# T35_3_POWERSUPPLY.net
KiCad netlist of a schematic drawn in Altium Designer
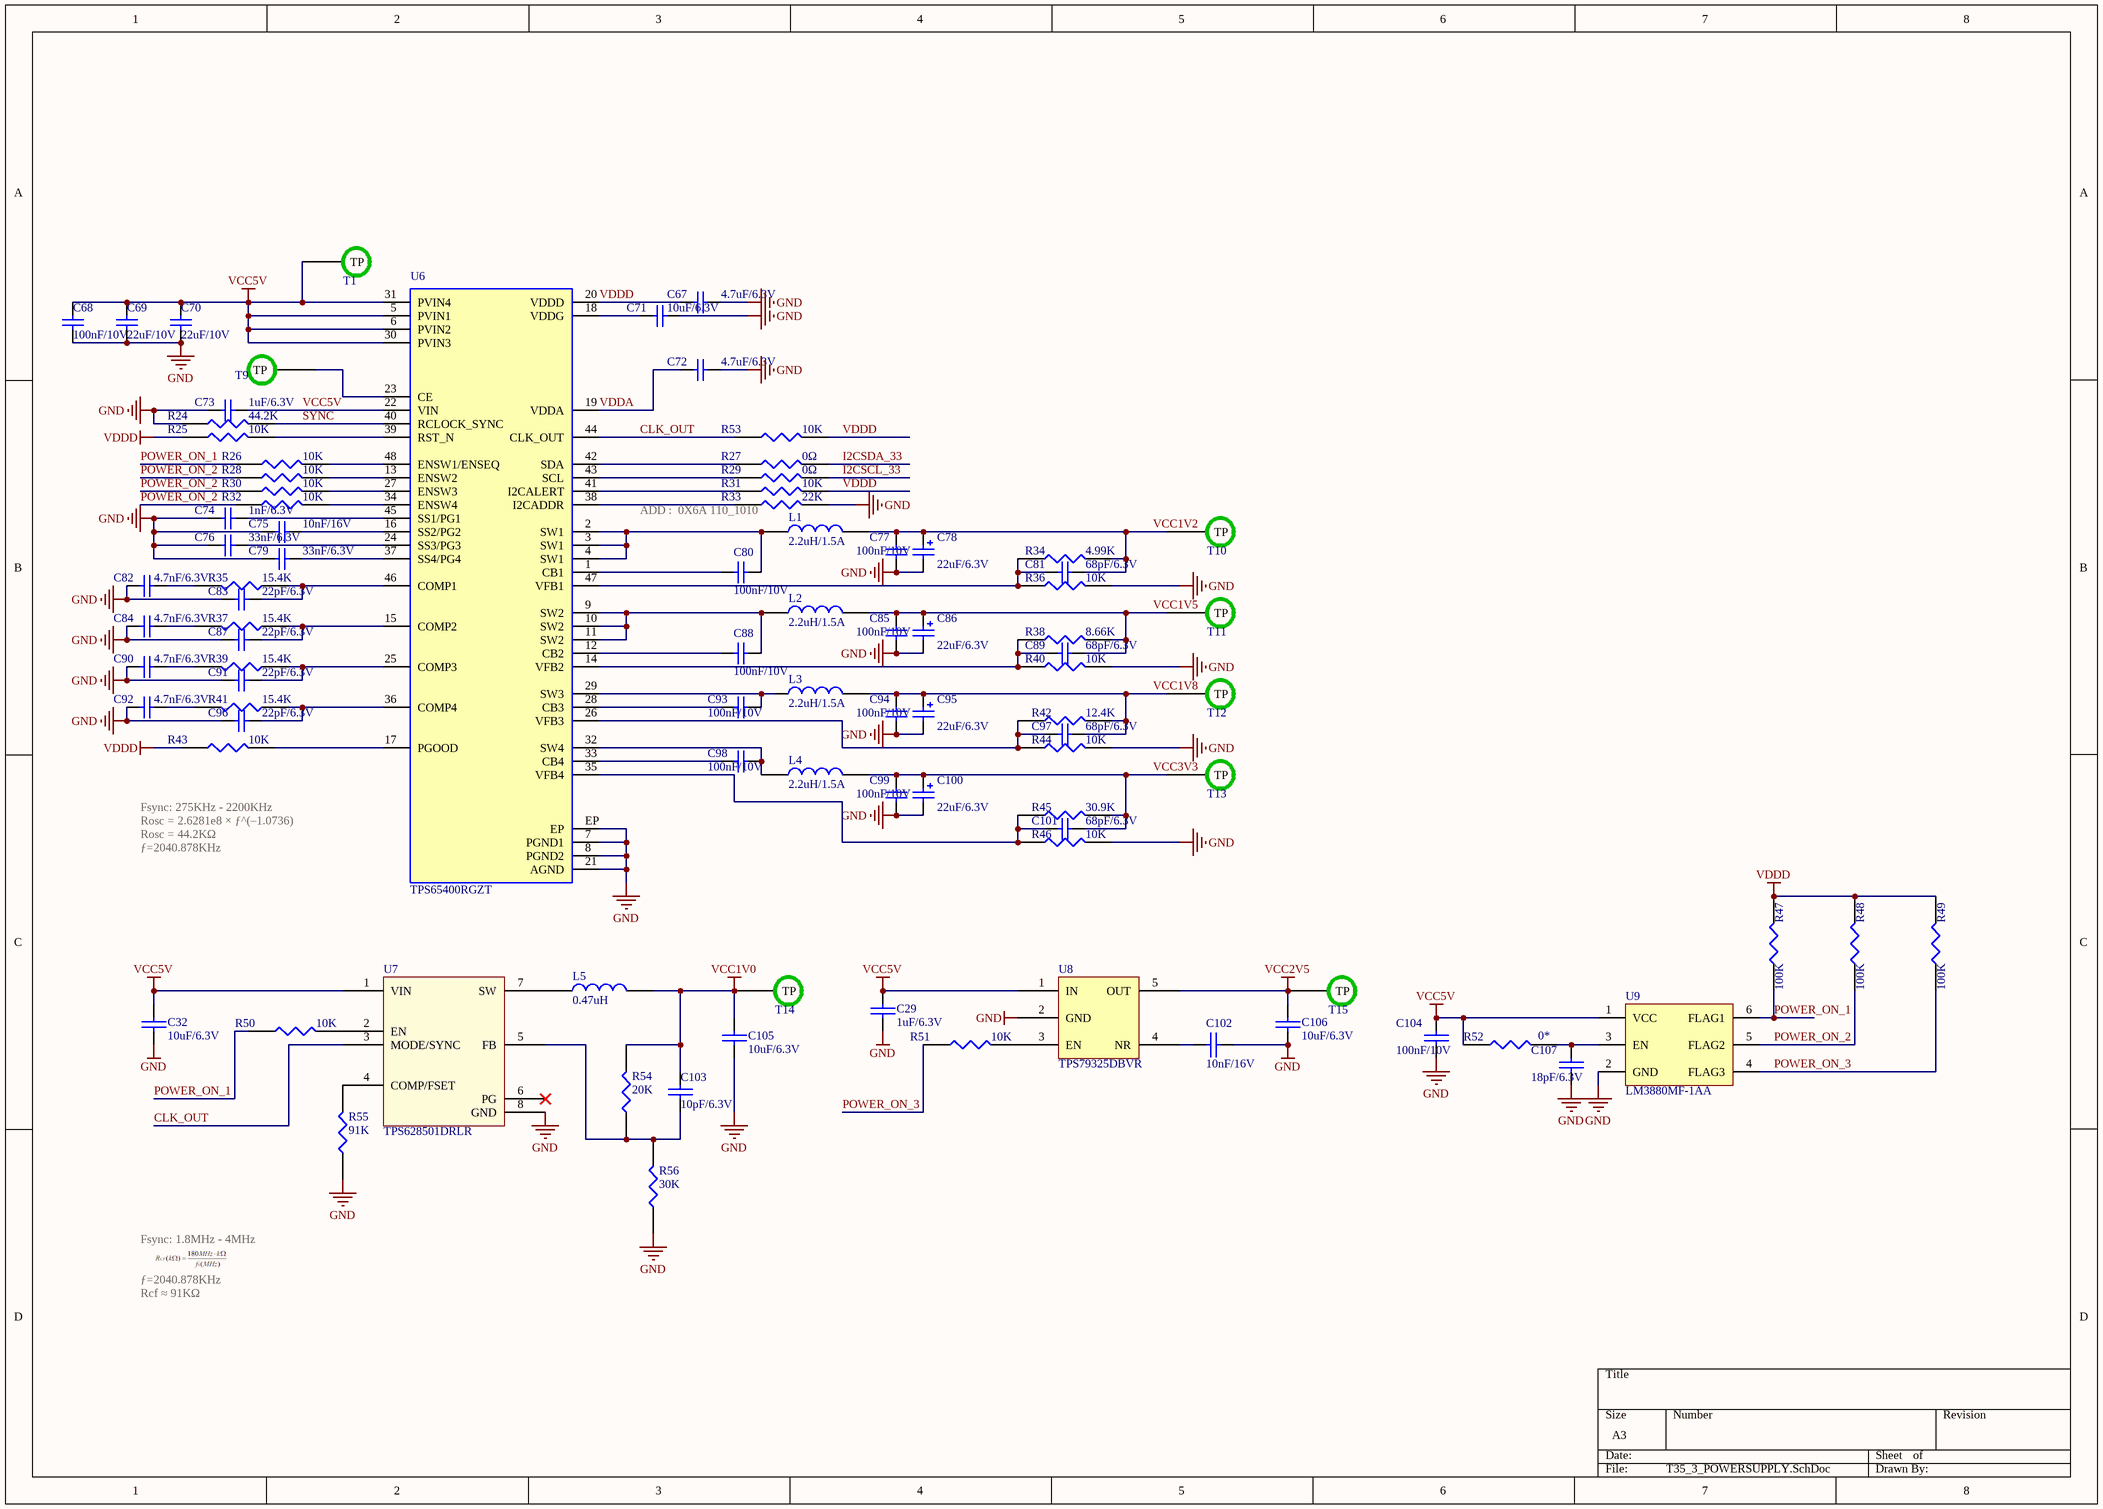
[diagram p0: T35_3_POWERSUPPLY.SchDoc]

(export (version "E")
  (design (tool "Eeschema 10.0.6"))
  (components
    (comp (ref "C29")
      (value "1uF/6.3V")
      (footprint "0201CS")
      (description "贴片电容")
      (libsource (lib "*") (part "CAP"))
    )
    (comp (ref "C32")
      (value "10uF/6.3V")
      (footprint "0402CS")
      (description "贴片电容")
      (libsource (lib "QHY_SCHLIB") (part "CAP"))
    )
    (comp (ref "C67")
      (value "4.7uF/6.3V")
      (footprint "0402CS")
      (description "贴片电容")
      (libsource (lib "Cap") (part "0402 100nF (104) 10% 16V"))
    )
    (comp (ref "C68")
      (value "100nF/10V")
      (footprint "0201CS")
      (description "贴片电容")
      (libsource (lib "Cap") (part "0402 100nF (104) 10% 16V"))
    )
    (comp (ref "C69")
      (value "22uF/10V")
      (footprint "0603CS")
      (description "贴片电容")
      (libsource (lib "Cap") (part "0402 100nF (104) 10% 16V"))
    )
    (comp (ref "C70")
      (value "22uF/10V")
      (footprint "0603CS")
      (description "贴片电容")
      (libsource (lib "Cap") (part "0402 100nF (104) 10% 16V"))
    )
    (comp (ref "C71")
      (value "10uF/6.3V")
      (footprint "0402CS")
      (description "贴片电容")
      (libsource (lib "Cap") (part "0402 100nF (104) 10% 16V"))
    )
    (comp (ref "C72")
      (value "4.7uF/6.3V")
      (footprint "0402CS")
      (description "贴片电容")
      (libsource (lib "Cap") (part "0402 100nF (104) 10% 16V"))
    )
    (comp (ref "C73")
      (value "1uF/6.3V")
      (footprint "0201CS")
      (description "贴片电容")
      (libsource (lib "Cap") (part "0402 100nF (104) 10% 16V"))
    )
    (comp (ref "C74")
      (value "1nF/6.3V")
      (footprint "0201CS")
      (description "贴片电容")
      (libsource (lib "Cap") (part "0402 100nF (104) 10% 16V"))
    )
    (comp (ref "C75")
      (value "10nF/16V")
      (footprint "0201CS")
      (description "贴片电容")
      (libsource (lib "Cap") (part "0402 100nF (104) 10% 16V"))
    )
    (comp (ref "C76")
      (value "33nF/6.3V")
      (footprint "0201CS")
      (description "贴片电容")
      (libsource (lib "Cap") (part "0402 100nF (104) 10% 16V"))
    )
    (comp (ref "C77")
      (value "100nF/10V")
      (footprint "0201CS")
      (description "贴片电容")
      (libsource (lib "Cap") (part "0402 100nF (104) 10% 16V"))
    )
    (comp (ref "C78")
      (value "22uF/6.3V")
      (footprint "0603CS")
      (description "贴片电容")
      (libsource (lib "Cap") (part "3216 10uF (106) 10% 16V"))
    )
    (comp (ref "C79")
      (value "33nF/6.3V")
      (footprint "0201CS")
      (description "贴片电容")
      (libsource (lib "Cap") (part "0402 100nF (104) 10% 16V"))
    )
    (comp (ref "C80")
      (value "100nF/10V")
      (footprint "0201CS")
      (description "贴片电容")
      (libsource (lib "Cap") (part "0402 100nF (104) 10% 16V"))
    )
    (comp (ref "C81")
      (value "68pF/6.3V")
      (footprint "0201CS")
      (description "贴片电容")
      (libsource (lib "Cap") (part "0402 100nF (104) 10% 16V"))
    )
    (comp (ref "C82")
      (value "4.7nF/6.3V")
      (footprint "0201CS")
      (description "贴片电容")
      (libsource (lib "Cap") (part "0402 100nF (104) 10% 16V"))
    )
    (comp (ref "C83")
      (value "22pF/6.3V")
      (footprint "0201CS")
      (description "贴片电容")
      (libsource (lib "Cap") (part "0402 100nF (104) 10% 16V"))
    )
    (comp (ref "C84")
      (value "4.7nF/6.3V")
      (footprint "0201CS")
      (description "贴片电容")
      (libsource (lib "Cap") (part "0402 100nF (104) 10% 16V"))
    )
    (comp (ref "C85")
      (value "100nF/10V")
      (footprint "0201CS")
      (description "贴片电容")
      (libsource (lib "Cap") (part "0402 100nF (104) 10% 16V"))
    )
    (comp (ref "C86")
      (value "22uF/6.3V")
      (footprint "0603CS")
      (description "贴片电容")
      (libsource (lib "Cap") (part "3216 10uF (106) 10% 16V"))
    )
    (comp (ref "C87")
      (value "22pF/6.3V")
      (footprint "0201CS")
      (description "贴片电容")
      (libsource (lib "Cap") (part "0402 100nF (104) 10% 16V"))
    )
    (comp (ref "C88")
      (value "100nF/10V")
      (footprint "0201CS")
      (description "贴片电容")
      (libsource (lib "Cap") (part "0402 100nF (104) 10% 16V"))
    )
    (comp (ref "C89")
      (value "68pF/6.3V")
      (footprint "0201CS")
      (description "贴片电容")
      (libsource (lib "Cap") (part "0402 100nF (104) 10% 16V"))
    )
    (comp (ref "C90")
      (value "4.7nF/6.3V")
      (footprint "0201CS")
      (description "贴片电容")
      (libsource (lib "Cap") (part "0402 100nF (104) 10% 16V"))
    )
    (comp (ref "C91")
      (value "22pF/6.3V")
      (footprint "0201CS")
      (description "贴片电容")
      (libsource (lib "Cap") (part "0402 100nF (104) 10% 16V"))
    )
    (comp (ref "C92")
      (value "4.7nF/6.3V")
      (footprint "0201CS")
      (description "贴片电容")
      (libsource (lib "Cap") (part "0402 100nF (104) 10% 16V"))
    )
    (comp (ref "C93")
      (value "100nF/10V")
      (footprint "0201CS")
      (description "贴片电容")
      (libsource (lib "Cap") (part "0402 100nF (104) 10% 16V"))
    )
    (comp (ref "C94")
      (value "100nF/10V")
      (footprint "0201CS")
      (description "贴片电容")
      (libsource (lib "Cap") (part "0402 100nF (104) 10% 16V"))
    )
    (comp (ref "C95")
      (value "22uF/6.3V")
      (footprint "0603CS")
      (description "贴片电容")
      (libsource (lib "Cap") (part "3216 10uF (106) 10% 16V"))
    )
    (comp (ref "C96")
      (value "22pF/6.3V")
      (footprint "0201CS")
      (description "贴片电容")
      (libsource (lib "Cap") (part "0402 100nF (104) 10% 16V"))
    )
    (comp (ref "C97")
      (value "68pF/6.3V")
      (footprint "0201CS")
      (description "贴片电容")
      (libsource (lib "Cap") (part "0402 100nF (104) 10% 16V"))
    )
    (comp (ref "C98")
      (value "100nF/10V")
      (footprint "0201CS")
      (description "贴片电容")
      (libsource (lib "Cap") (part "0402 100nF (104) 10% 16V"))
    )
    (comp (ref "C99")
      (value "100nF/10V")
      (footprint "0201CS")
      (description "贴片电容")
      (libsource (lib "Cap") (part "0402 100nF (104) 10% 16V"))
    )
    (comp (ref "C100")
      (value "22uF/6.3V")
      (footprint "0603CS")
      (description "贴片电容")
      (libsource (lib "Cap") (part "3216 10uF (106) 10% 16V"))
    )
    (comp (ref "C101")
      (value "68pF/6.3V")
      (footprint "0201CS")
      (description "贴片电容")
      (libsource (lib "Cap") (part "0402 100nF (104) 10% 16V"))
    )
    (comp (ref "C102")
      (value "10nF/16V")
      (footprint "0201CS")
      (description "贴片电容")
      (libsource (lib "*") (part "CAP"))
    )
    (comp (ref "C103")
      (value "10pF/6.3V")
      (footprint "0201CS")
      (description "贴片电容")
      (libsource (lib "QHY_SCHLIB") (part "CAP"))
    )
    (comp (ref "C104")
      (value "100nF/10V")
      (footprint "0201CS")
      (description "贴片电容")
      (libsource (lib "*") (part "CAP"))
    )
    (comp (ref "C105")
      (value "10uF/6.3V")
      (footprint "0402CS")
      (description "贴片电容")
      (libsource (lib "QHY_SCHLIB") (part "CAP"))
    )
    (comp (ref "C106")
      (value "10uF/6.3V")
      (footprint "0402CS")
      (description "贴片电容")
      (libsource (lib "QHY_SCHLIB") (part "CAP"))
    )
    (comp (ref "C107")
      (value "18pF/6.3V")
      (footprint "0201CS")
      (description "贴片电容")
      (libsource (lib "*") (part "CAP"))
    )
    (comp (ref "L1")
      (value "2.2uH/1.5A")
      (footprint "201610")
      (description "功率电感")
      (libsource (lib "QHY_SCHLIB") (part "INDUCTOR"))
    )
    (comp (ref "L2")
      (value "2.2uH/1.5A")
      (footprint "201610")
      (description "功率电感")
      (libsource (lib "QHY_SCHLIB") (part "INDUCTOR"))
    )
    (comp (ref "L3")
      (value "2.2uH/1.5A")
      (footprint "201610")
      (description "功率电感")
      (libsource (lib "QHY_SCHLIB") (part "INDUCTOR"))
    )
    (comp (ref "L4")
      (value "2.2uH/1.5A")
      (footprint "201610")
      (description "功率电感")
      (libsource (lib "QHY_SCHLIB") (part "INDUCTOR"))
    )
    (comp (ref "L5")
      (value "0.47uH")
      (footprint "201610")
      (description "功率电感")
      (fields (field (name "PARTNUMBER") "BDCD00201610R47MS1"))
      (libsource (lib "QHY_SCHLIB") (part "INDUCTOR"))
    )
    (comp (ref "R24")
      (value "44.2K")
      (footprint "0201RS")
      (description "贴片电阻")
      (libsource (lib "*") (part "RES1"))
    )
    (comp (ref "R25")
      (value "10K")
      (footprint "0201RS")
      (description "贴片电阻")
      (libsource (lib "*") (part "RES1"))
    )
    (comp (ref "R26")
      (value "10K")
      (footprint "0201RS")
      (description "贴片电阻")
      (libsource (lib "*") (part "RES1"))
    )
    (comp (ref "R27")
      (value "0Ω")
      (footprint "0201RS")
      (description "贴片电阻")
      (libsource (lib "*") (part "RES1"))
    )
    (comp (ref "R28")
      (value "10K")
      (footprint "0201RS")
      (description "贴片电阻")
      (libsource (lib "*") (part "RES1"))
    )
    (comp (ref "R29")
      (value "0Ω")
      (footprint "0201RS")
      (description "贴片电阻")
      (libsource (lib "*") (part "RES1"))
    )
    (comp (ref "R30")
      (value "10K")
      (footprint "0201RS")
      (description "贴片电阻")
      (libsource (lib "*") (part "RES1"))
    )
    (comp (ref "R31")
      (value "10K")
      (footprint "0201RS")
      (description "贴片电阻")
      (libsource (lib "*") (part "RES1"))
    )
    (comp (ref "R32")
      (value "10K")
      (footprint "0201RS")
      (description "贴片电阻")
      (libsource (lib "*") (part "RES1"))
    )
    (comp (ref "R33")
      (value "22K")
      (footprint "0201RS")
      (description "贴片电阻")
      (libsource (lib "*") (part "RES1"))
    )
    (comp (ref "R34")
      (value "4.99K")
      (footprint "0201RS")
      (description "贴片电阻")
      (libsource (lib "*") (part "RES1"))
    )
    (comp (ref "R35")
      (value "15.4K")
      (footprint "0201RS")
      (description "贴片电阻")
      (libsource (lib "*") (part "RES1"))
    )
    (comp (ref "R36")
      (value "10K")
      (footprint "0201RS")
      (description "贴片电阻")
      (libsource (lib "*") (part "RES1"))
    )
    (comp (ref "R37")
      (value "15.4K")
      (footprint "0201RS")
      (description "贴片电阻")
      (libsource (lib "*") (part "RES1"))
    )
    (comp (ref "R38")
      (value "8.66K")
      (footprint "0201RS")
      (description "贴片电阻")
      (libsource (lib "*") (part "RES1"))
    )
    (comp (ref "R39")
      (value "15.4K")
      (footprint "0201RS")
      (description "贴片电阻")
      (libsource (lib "*") (part "RES1"))
    )
    (comp (ref "R40")
      (value "10K")
      (footprint "0201RS")
      (description "贴片电阻")
      (libsource (lib "*") (part "RES1"))
    )
    (comp (ref "R41")
      (value "15.4K")
      (footprint "0201RS")
      (description "贴片电阻")
      (libsource (lib "*") (part "RES1"))
    )
    (comp (ref "R42")
      (value "12.4K")
      (footprint "0201RS")
      (description "贴片电阻")
      (libsource (lib "*") (part "RES1"))
    )
    (comp (ref "R43")
      (value "10K")
      (footprint "0201RS")
      (description "贴片电阻")
      (libsource (lib "*") (part "RES1"))
    )
    (comp (ref "R44")
      (value "10K")
      (footprint "0201RS")
      (description "贴片电阻")
      (libsource (lib "*") (part "RES1"))
    )
    (comp (ref "R45")
      (value "30.9K")
      (footprint "0201RS")
      (description "贴片电阻")
      (libsource (lib "*") (part "RES1"))
    )
    (comp (ref "R46")
      (value "10K")
      (footprint "0201RS")
      (description "贴片电阻")
      (libsource (lib "*") (part "RES1"))
    )
    (comp (ref "R47")
      (value "100K")
      (footprint "0201RS")
      (description "贴片电阻")
      (libsource (lib "*") (part "RES1"))
    )
    (comp (ref "R48")
      (value "100K")
      (footprint "0201RS")
      (description "贴片电阻")
      (libsource (lib "*") (part "RES1"))
    )
    (comp (ref "R49")
      (value "100K")
      (footprint "0201RS")
      (description "贴片电阻")
      (libsource (lib "*") (part "RES1"))
    )
    (comp (ref "R50")
      (value "10K")
      (footprint "0201RS")
      (description "贴片电阻")
      (libsource (lib "*") (part "RES1"))
    )
    (comp (ref "R51")
      (value "10K")
      (footprint "0201RS")
      (description "贴片电阻")
      (libsource (lib "*") (part "RES1"))
    )
    (comp (ref "R52")
      (value "0*")
      (footprint "0201RS")
      (description "贴片电阻")
      (libsource (lib "*") (part "RES1"))
    )
    (comp (ref "R53")
      (value "10K")
      (footprint "0201RS")
      (description "贴片电阻")
      (libsource (lib "*") (part "RES1"))
    )
    (comp (ref "R54")
      (value "20K")
      (footprint "0201RS")
      (description "贴片电阻")
      (libsource (lib "*") (part "RES1"))
    )
    (comp (ref "R55")
      (value "91K")
      (footprint "0201RS")
      (description "贴片电阻")
      (libsource (lib "*") (part "RES1"))
    )
    (comp (ref "R56")
      (value "30K")
      (footprint "0201RS")
      (description "贴片电阻")
      (libsource (lib "*") (part "RES1"))
    )
    (comp (ref "T1")
      (value "~")
      (footprint "TP-S")
      (description "测试点")
      (libsource (lib "QHY_SCHLIB") (part "TP"))
    )
    (comp (ref "T9")
      (value "~")
      (footprint "TP-S")
      (description "测试点")
      (libsource (lib "QHY_SCHLIB") (part "TP"))
    )
    (comp (ref "T10")
      (value "~")
      (footprint "TP-S")
      (description "测试点")
      (libsource (lib "QHY_SCHLIB") (part "TP"))
    )
    (comp (ref "T11")
      (value "~")
      (footprint "TP-S")
      (description "测试点")
      (libsource (lib "QHY_SCHLIB") (part "TP"))
    )
    (comp (ref "T12")
      (value "~")
      (footprint "TP-S")
      (description "测试点")
      (libsource (lib "QHY_SCHLIB") (part "TP"))
    )
    (comp (ref "T13")
      (value "~")
      (footprint "TP-S")
      (description "测试点")
      (libsource (lib "QHY_SCHLIB") (part "TP"))
    )
    (comp (ref "T14")
      (value "~")
      (footprint "TP-S")
      (description "测试点")
      (libsource (lib "QHY_SCHLIB") (part "TP"))
    )
    (comp (ref "T15")
      (value "~")
      (footprint "TP-S")
      (description "测试点")
      (libsource (lib "QHY_SCHLIB") (part "TP"))
    )
    (comp (ref "U6")
      (value "TPS65400RGZT")
      (footprint "QFN50P700X700X100-49N_TPS65400RGZT(Primary)")
      (description "电源芯片")
      (fields (field (name "MF") "Texas Instruments"))
      (libsource (lib "QHY_CMOS_POWER_V1") (part "TPS65400RGZT"))
    )
    (comp (ref "U7")
      (value "TPS628501DRLR")
      (footprint "SOT583")
      (description "电源芯片")
      (libsource (lib "T35-V2") (part "TPS628501"))
    )
    (comp (ref "U8")
      (value "TPS79325DBVR")
      (footprint "SOT-23-5")
      (description "电源芯片")
      (libsource (lib "QHY_SCHLIB") (part "TPS793-XX"))
    )
    (comp (ref "U9")
      (value "LM3880MF-1AA")
      (footprint "SOT-23-6")
      (description "时序排序器")
      (libsource (lib "IMX411_V1") (part "LM3880MF-1AA"))
    )
  )
  (nets
    (net (code "1") (name "/CLK_OUT") (class "Default")
      (node (ref "R53") (pin "1") (pinfunction "1_1") (pintype "passive"))
      (node (ref "U6") (pin "44") (pinfunction "CLK_OUT_44") (pintype "passive"))
      (node (ref "U7") (pin "3") (pinfunction "MODE/SYNC_3") (pintype "passive"))
    )
    (net (code "2") (name "/I2CSCL_33") (class "Default")
      (node (ref "R29") (pin "2") (pinfunction "2_2") (pintype "passive"))
    )
    (net (code "3") (name "/I2CSDA_33") (class "Default")
      (node (ref "R27") (pin "2") (pinfunction "2_2") (pintype "passive"))
    )
    (net (code "4") (name "/POWER_ON_1") (class "Default")
      (node (ref "R26") (pin "1") (pinfunction "1_1") (pintype "passive"))
      (node (ref "R47") (pin "1") (pinfunction "1_1") (pintype "passive"))
      (node (ref "R50") (pin "1") (pinfunction "1_1") (pintype "passive"))
      (node (ref "U9") (pin "6") (pinfunction "FLAG1_6") (pintype "passive"))
    )
    (net (code "5") (name "/POWER_ON_2") (class "Default")
      (node (ref "R28") (pin "1") (pinfunction "1_1") (pintype "passive"))
      (node (ref "R30") (pin "1") (pinfunction "1_1") (pintype "passive"))
      (node (ref "R32") (pin "1") (pinfunction "1_1") (pintype "passive"))
      (node (ref "R48") (pin "1") (pinfunction "1_1") (pintype "passive"))
      (node (ref "U9") (pin "5") (pinfunction "FLAG2_5") (pintype "passive"))
    )
    (net (code "6") (name "/POWER_ON_3") (class "Default")
      (node (ref "R49") (pin "1") (pinfunction "1_1") (pintype "passive"))
      (node (ref "R51") (pin "1") (pinfunction "1_1") (pintype "passive"))
      (node (ref "U9") (pin "4") (pinfunction "FLAG3_4") (pintype "passive"))
    )
    (net (code "7") (name "/SYNC") (class "Default")
      (node (ref "R24") (pin "2") (pinfunction "2_2") (pintype "passive"))
      (node (ref "U6") (pin "40") (pinfunction "RCLOCK_SYNC_40") (pintype "passive"))
    )
    (net (code "8") (name "/VCC1V2") (class "Default")
      (node (ref "C77") (pin "2") (pinfunction "2_2") (pintype "passive"))
      (node (ref "C78") (pin "1") (pinfunction "1_1") (pintype "passive"))
      (node (ref "C81") (pin "1") (pinfunction "1_1") (pintype "passive"))
      (node (ref "L1") (pin "2") (pinfunction "2_2") (pintype "passive"))
      (node (ref "R34") (pin "2") (pinfunction "2_2") (pintype "passive"))
      (node (ref "T10") (pin "1") (pinfunction "TP_1") (pintype "passive"))
    )
    (net (code "9") (name "/VCC1V5") (class "Default")
      (node (ref "C85") (pin "2") (pinfunction "2_2") (pintype "passive"))
      (node (ref "C86") (pin "1") (pinfunction "1_1") (pintype "passive"))
      (node (ref "C89") (pin "1") (pinfunction "1_1") (pintype "passive"))
      (node (ref "L2") (pin "2") (pinfunction "2_2") (pintype "passive"))
      (node (ref "R38") (pin "2") (pinfunction "2_2") (pintype "passive"))
      (node (ref "T11") (pin "1") (pinfunction "TP_1") (pintype "passive"))
    )
    (net (code "10") (name "/VCC1V8") (class "Default")
      (node (ref "C94") (pin "2") (pinfunction "2_2") (pintype "passive"))
      (node (ref "C95") (pin "1") (pinfunction "1_1") (pintype "passive"))
      (node (ref "C97") (pin "1") (pinfunction "1_1") (pintype "passive"))
      (node (ref "L3") (pin "2") (pinfunction "2_2") (pintype "passive"))
      (node (ref "R42") (pin "2") (pinfunction "2_2") (pintype "passive"))
      (node (ref "T12") (pin "1") (pinfunction "TP_1") (pintype "passive"))
    )
    (net (code "11") (name "/VCC3V3") (class "Default")
      (node (ref "C100") (pin "1") (pinfunction "1_1") (pintype "passive"))
      (node (ref "C101") (pin "1") (pinfunction "1_1") (pintype "passive"))
      (node (ref "C99") (pin "2") (pinfunction "2_2") (pintype "passive"))
      (node (ref "L4") (pin "2") (pinfunction "2_2") (pintype "passive"))
      (node (ref "R45") (pin "2") (pinfunction "2_2") (pintype "passive"))
      (node (ref "T13") (pin "1") (pinfunction "TP_1") (pintype "passive"))
    )
    (net (code "12") (name "/VDDA") (class "Default")
      (node (ref "C72") (pin "1") (pinfunction "1_1") (pintype "passive"))
      (node (ref "U6") (pin "19") (pinfunction "VDDA_19") (pintype "passive"))
    )
    (net (code "13") (name "GND") (class "Default")
      (node (ref "C100") (pin "2") (pinfunction "2_2") (pintype "passive"))
      (node (ref "C102") (pin "2") (pinfunction "2_2") (pintype "passive"))
      (node (ref "C104") (pin "2") (pinfunction "2_2") (pintype "passive"))
      (node (ref "C105") (pin "2") (pinfunction "2_2") (pintype "passive"))
      (node (ref "C106") (pin "2") (pinfunction "2_2") (pintype "passive"))
      (node (ref "C107") (pin "2") (pinfunction "2_2") (pintype "passive"))
      (node (ref "C29") (pin "2") (pinfunction "2_2") (pintype "passive"))
      (node (ref "C32") (pin "2") (pinfunction "2_2") (pintype "passive"))
      (node (ref "C67") (pin "2") (pinfunction "2_2") (pintype "passive"))
      (node (ref "C68") (pin "1") (pinfunction "1_1") (pintype "passive"))
      (node (ref "C69") (pin "1") (pinfunction "1_1") (pintype "passive"))
      (node (ref "C70") (pin "1") (pinfunction "1_1") (pintype "passive"))
      (node (ref "C71") (pin "2") (pinfunction "2_2") (pintype "passive"))
      (node (ref "C72") (pin "2") (pinfunction "2_2") (pintype "passive"))
      (node (ref "C73") (pin "1") (pinfunction "1_1") (pintype "passive"))
      (node (ref "C74") (pin "1") (pinfunction "1_1") (pintype "passive"))
      (node (ref "C75") (pin "1") (pinfunction "1_1") (pintype "passive"))
      (node (ref "C76") (pin "1") (pinfunction "1_1") (pintype "passive"))
      (node (ref "C77") (pin "1") (pinfunction "1_1") (pintype "passive"))
      (node (ref "C78") (pin "2") (pinfunction "2_2") (pintype "passive"))
      (node (ref "C79") (pin "1") (pinfunction "1_1") (pintype "passive"))
      (node (ref "C82") (pin "2") (pinfunction "2_2") (pintype "passive"))
      (node (ref "C83") (pin "2") (pinfunction "2_2") (pintype "passive"))
      (node (ref "C84") (pin "2") (pinfunction "2_2") (pintype "passive"))
      (node (ref "C85") (pin "1") (pinfunction "1_1") (pintype "passive"))
      (node (ref "C86") (pin "2") (pinfunction "2_2") (pintype "passive"))
      (node (ref "C87") (pin "2") (pinfunction "2_2") (pintype "passive"))
      (node (ref "C90") (pin "2") (pinfunction "2_2") (pintype "passive"))
      (node (ref "C91") (pin "2") (pinfunction "2_2") (pintype "passive"))
      (node (ref "C92") (pin "2") (pinfunction "2_2") (pintype "passive"))
      (node (ref "C94") (pin "1") (pinfunction "1_1") (pintype "passive"))
      (node (ref "C95") (pin "2") (pinfunction "2_2") (pintype "passive"))
      (node (ref "C96") (pin "2") (pinfunction "2_2") (pintype "passive"))
      (node (ref "C99") (pin "1") (pinfunction "1_1") (pintype "passive"))
      (node (ref "R24") (pin "1") (pinfunction "1_1") (pintype "passive"))
      (node (ref "R33") (pin "2") (pinfunction "2_2") (pintype "passive"))
      (node (ref "R36") (pin "2") (pinfunction "2_2") (pintype "passive"))
      (node (ref "R40") (pin "2") (pinfunction "2_2") (pintype "passive"))
      (node (ref "R44") (pin "2") (pinfunction "2_2") (pintype "passive"))
      (node (ref "R46") (pin "2") (pinfunction "2_2") (pintype "passive"))
      (node (ref "R55") (pin "1") (pinfunction "1_1") (pintype "passive"))
      (node (ref "R56") (pin "1") (pinfunction "1_1") (pintype "passive"))
      (node (ref "U6") (pin "21") (pinfunction "AGND_21") (pintype "power_in"))
      (node (ref "U6") (pin "7") (pinfunction "PGND1_7") (pintype "power_in"))
      (node (ref "U6") (pin "8") (pinfunction "PGND2_8") (pintype "power_in"))
      (node (ref "U6") (pin "EP") (pinfunction "EP_EP") (pintype "power_in"))
      (node (ref "U7") (pin "8") (pinfunction "GND_8") (pintype "passive"))
      (node (ref "U8") (pin "2") (pinfunction "GND_2") (pintype "passive"))
      (node (ref "U9") (pin "2") (pinfunction "GND_2") (pintype "passive"))
    )
    (net (code "14") (name "Net-(C80-Pad1)") (class "Default")
      (node (ref "C80") (pin "1") (pinfunction "1_1") (pintype "passive"))
      (node (ref "L1") (pin "1") (pinfunction "1_1") (pintype "passive"))
      (node (ref "U6") (pin "2") (pinfunction "SW1_2") (pintype "passive"))
      (node (ref "U6") (pin "3") (pinfunction "SW1_3") (pintype "passive"))
      (node (ref "U6") (pin "4") (pinfunction "SW1_4") (pintype "passive"))
    )
    (net (code "15") (name "Net-(C82-Pad1)") (class "Default")
      (node (ref "C82") (pin "1") (pinfunction "1_1") (pintype "passive"))
      (node (ref "R35") (pin "2") (pinfunction "2_2") (pintype "passive"))
    )
    (net (code "16") (name "Net-(C84-Pad1)") (class "Default")
      (node (ref "C84") (pin "1") (pinfunction "1_1") (pintype "passive"))
      (node (ref "R37") (pin "2") (pinfunction "2_2") (pintype "passive"))
    )
    (net (code "17") (name "Net-(C88-Pad1)") (class "Default")
      (node (ref "C88") (pin "1") (pinfunction "1_1") (pintype "passive"))
      (node (ref "L2") (pin "1") (pinfunction "1_1") (pintype "passive"))
      (node (ref "U6") (pin "10") (pinfunction "SW2_10") (pintype "passive"))
      (node (ref "U6") (pin "11") (pinfunction "SW2_11") (pintype "passive"))
      (node (ref "U6") (pin "9") (pinfunction "SW2_9") (pintype "passive"))
    )
    (net (code "18") (name "Net-(C90-Pad1)") (class "Default")
      (node (ref "C90") (pin "1") (pinfunction "1_1") (pintype "passive"))
      (node (ref "R39") (pin "2") (pinfunction "2_2") (pintype "passive"))
    )
    (net (code "19") (name "Net-(C92-Pad1)") (class "Default")
      (node (ref "C92") (pin "1") (pinfunction "1_1") (pintype "passive"))
      (node (ref "R41") (pin "2") (pinfunction "2_2") (pintype "passive"))
    )
    (net (code "20") (name "Net-(T9-TP)") (class "Default")
      (node (ref "T9") (pin "1") (pinfunction "TP_1") (pintype "passive"))
      (node (ref "U6") (pin "23") (pinfunction "CE_23") (pintype "passive"))
    )
    (net (code "21") (name "Net-(U6-CB1)") (class "Default")
      (node (ref "C80") (pin "2") (pinfunction "2_2") (pintype "passive"))
      (node (ref "U6") (pin "1") (pinfunction "CB1_1") (pintype "passive"))
    )
    (net (code "22") (name "Net-(U6-CB2)") (class "Default")
      (node (ref "C88") (pin "2") (pinfunction "2_2") (pintype "passive"))
      (node (ref "U6") (pin "12") (pinfunction "CB2_12") (pintype "passive"))
    )
    (net (code "23") (name "Net-(U6-CB3)") (class "Default")
      (node (ref "C93") (pin "2") (pinfunction "2_2") (pintype "passive"))
      (node (ref "U6") (pin "28") (pinfunction "CB3_28") (pintype "passive"))
    )
    (net (code "24") (name "Net-(U6-CB4)") (class "Default")
      (node (ref "C98") (pin "2") (pinfunction "2_2") (pintype "passive"))
      (node (ref "U6") (pin "33") (pinfunction "CB4_33") (pintype "passive"))
    )
    (net (code "25") (name "Net-(U6-COMP1)") (class "Default")
      (node (ref "C83") (pin "1") (pinfunction "1_1") (pintype "passive"))
      (node (ref "R35") (pin "1") (pinfunction "1_1") (pintype "passive"))
      (node (ref "U6") (pin "46") (pinfunction "COMP1_46") (pintype "passive"))
    )
    (net (code "26") (name "Net-(U6-COMP2)") (class "Default")
      (node (ref "C87") (pin "1") (pinfunction "1_1") (pintype "passive"))
      (node (ref "R37") (pin "1") (pinfunction "1_1") (pintype "passive"))
      (node (ref "U6") (pin "15") (pinfunction "COMP2_15") (pintype "passive"))
    )
    (net (code "27") (name "Net-(U6-COMP3)") (class "Default")
      (node (ref "C91") (pin "1") (pinfunction "1_1") (pintype "passive"))
      (node (ref "R39") (pin "1") (pinfunction "1_1") (pintype "passive"))
      (node (ref "U6") (pin "25") (pinfunction "COMP3_25") (pintype "passive"))
    )
    (net (code "28") (name "Net-(U6-COMP4)") (class "Default")
      (node (ref "C96") (pin "1") (pinfunction "1_1") (pintype "passive"))
      (node (ref "R41") (pin "1") (pinfunction "1_1") (pintype "passive"))
      (node (ref "U6") (pin "36") (pinfunction "COMP4_36") (pintype "passive"))
    )
    (net (code "29") (name "Net-(U6-ENSW1{slash}ENSEQ)") (class "Default")
      (node (ref "R26") (pin "2") (pinfunction "2_2") (pintype "passive"))
      (node (ref "U6") (pin "48") (pinfunction "ENSW1/ENSEQ_48") (pintype "passive"))
    )
    (net (code "30") (name "Net-(U6-ENSW2)") (class "Default")
      (node (ref "R28") (pin "2") (pinfunction "2_2") (pintype "passive"))
      (node (ref "U6") (pin "13") (pinfunction "ENSW2_13") (pintype "passive"))
    )
    (net (code "31") (name "Net-(U6-ENSW3)") (class "Default")
      (node (ref "R30") (pin "2") (pinfunction "2_2") (pintype "passive"))
      (node (ref "U6") (pin "27") (pinfunction "ENSW3_27") (pintype "passive"))
    )
    (net (code "32") (name "Net-(U6-ENSW4)") (class "Default")
      (node (ref "R32") (pin "2") (pinfunction "2_2") (pintype "passive"))
      (node (ref "U6") (pin "34") (pinfunction "ENSW4_34") (pintype "passive"))
    )
    (net (code "33") (name "Net-(U6-I2CADDR)") (class "Default")
      (node (ref "R33") (pin "1") (pinfunction "1_1") (pintype "passive"))
      (node (ref "U6") (pin "38") (pinfunction "I2CADDR_38") (pintype "passive"))
    )
    (net (code "34") (name "Net-(U6-I2CALERT)") (class "Default")
      (node (ref "R31") (pin "1") (pinfunction "1_1") (pintype "passive"))
      (node (ref "U6") (pin "41") (pinfunction "I2CALERT_41") (pintype "passive"))
    )
    (net (code "35") (name "Net-(U6-PGOOD)") (class "Default")
      (node (ref "R43") (pin "2") (pinfunction "2_2") (pintype "passive"))
      (node (ref "U6") (pin "17") (pinfunction "PGOOD_17") (pintype "passive"))
    )
    (net (code "36") (name "Net-(U6-RST_N)") (class "Default")
      (node (ref "R25") (pin "2") (pinfunction "2_2") (pintype "passive"))
      (node (ref "U6") (pin "39") (pinfunction "RST_N_39") (pintype "passive"))
    )
    (net (code "37") (name "Net-(U6-SCL)") (class "Default")
      (node (ref "R29") (pin "1") (pinfunction "1_1") (pintype "passive"))
      (node (ref "U6") (pin "43") (pinfunction "SCL_43") (pintype "passive"))
    )
    (net (code "38") (name "Net-(U6-SDA)") (class "Default")
      (node (ref "R27") (pin "1") (pinfunction "1_1") (pintype "passive"))
      (node (ref "U6") (pin "42") (pinfunction "SDA_42") (pintype "passive"))
    )
    (net (code "39") (name "Net-(U6-SS1{slash}PG1)") (class "Default")
      (node (ref "C74") (pin "2") (pinfunction "2_2") (pintype "passive"))
      (node (ref "U6") (pin "45") (pinfunction "SS1/PG1_45") (pintype "passive"))
    )
    (net (code "40") (name "Net-(U6-SS2{slash}PG2)") (class "Default")
      (node (ref "C75") (pin "2") (pinfunction "2_2") (pintype "passive"))
      (node (ref "U6") (pin "16") (pinfunction "SS2/PG2_16") (pintype "passive"))
    )
    (net (code "41") (name "Net-(U6-SS3{slash}PG3)") (class "Default")
      (node (ref "C76") (pin "2") (pinfunction "2_2") (pintype "passive"))
      (node (ref "U6") (pin "24") (pinfunction "SS3/PG3_24") (pintype "passive"))
    )
    (net (code "42") (name "Net-(U6-SS4{slash}PG4)") (class "Default")
      (node (ref "C79") (pin "2") (pinfunction "2_2") (pintype "passive"))
      (node (ref "U6") (pin "37") (pinfunction "SS4/PG4_37") (pintype "passive"))
    )
    (net (code "43") (name "Net-(U6-SW3)") (class "Default")
      (node (ref "C93") (pin "1") (pinfunction "1_1") (pintype "passive"))
      (node (ref "L3") (pin "1") (pinfunction "1_1") (pintype "passive"))
      (node (ref "U6") (pin "29") (pinfunction "SW3_29") (pintype "passive"))
    )
    (net (code "44") (name "Net-(U6-SW4)") (class "Default")
      (node (ref "C98") (pin "1") (pinfunction "1_1") (pintype "passive"))
      (node (ref "L4") (pin "1") (pinfunction "1_1") (pintype "passive"))
      (node (ref "U6") (pin "32") (pinfunction "SW4_32") (pintype "passive"))
    )
    (net (code "45") (name "Net-(U6-VDDG)") (class "Default")
      (node (ref "C71") (pin "1") (pinfunction "1_1") (pintype "passive"))
      (node (ref "U6") (pin "18") (pinfunction "VDDG_18") (pintype "power_in"))
    )
    (net (code "46") (name "Net-(U6-VFB1)") (class "Default")
      (node (ref "C81") (pin "2") (pinfunction "2_2") (pintype "passive"))
      (node (ref "R34") (pin "1") (pinfunction "1_1") (pintype "passive"))
      (node (ref "R36") (pin "1") (pinfunction "1_1") (pintype "passive"))
      (node (ref "U6") (pin "47") (pinfunction "VFB1_47") (pintype "passive"))
    )
    (net (code "47") (name "Net-(U6-VFB2)") (class "Default")
      (node (ref "C89") (pin "2") (pinfunction "2_2") (pintype "passive"))
      (node (ref "R38") (pin "1") (pinfunction "1_1") (pintype "passive"))
      (node (ref "R40") (pin "1") (pinfunction "1_1") (pintype "passive"))
      (node (ref "U6") (pin "14") (pinfunction "VFB2_14") (pintype "passive"))
    )
    (net (code "48") (name "Net-(U6-VFB3)") (class "Default")
      (node (ref "C97") (pin "2") (pinfunction "2_2") (pintype "passive"))
      (node (ref "R42") (pin "1") (pinfunction "1_1") (pintype "passive"))
      (node (ref "R44") (pin "1") (pinfunction "1_1") (pintype "passive"))
      (node (ref "U6") (pin "26") (pinfunction "VFB3_26") (pintype "passive"))
    )
    (net (code "49") (name "Net-(U6-VFB4)") (class "Default")
      (node (ref "C101") (pin "2") (pinfunction "2_2") (pintype "passive"))
      (node (ref "R45") (pin "1") (pinfunction "1_1") (pintype "passive"))
      (node (ref "R46") (pin "1") (pinfunction "1_1") (pintype "passive"))
      (node (ref "U6") (pin "35") (pinfunction "VFB4_35") (pintype "passive"))
    )
    (net (code "50") (name "Net-(U7-COMP{slash}FSET)") (class "Default")
      (node (ref "R55") (pin "2") (pinfunction "2_2") (pintype "passive"))
      (node (ref "U7") (pin "4") (pinfunction "COMP/FSET_4") (pintype "passive"))
    )
    (net (code "51") (name "Net-(U7-EN)") (class "Default")
      (node (ref "R50") (pin "2") (pinfunction "2_2") (pintype "passive"))
      (node (ref "U7") (pin "2") (pinfunction "EN_2") (pintype "passive"))
    )
    (net (code "52") (name "Net-(U7-FB)") (class "Default")
      (node (ref "C103") (pin "2") (pinfunction "2_2") (pintype "passive"))
      (node (ref "R54") (pin "1") (pinfunction "1_1") (pintype "passive"))
      (node (ref "R56") (pin "2") (pinfunction "2_2") (pintype "passive"))
      (node (ref "U7") (pin "5") (pinfunction "FB_5") (pintype "passive"))
    )
    (net (code "53") (name "Net-(U7-SW)") (class "Default")
      (node (ref "L5") (pin "1") (pinfunction "1_1") (pintype "passive"))
      (node (ref "U7") (pin "7") (pinfunction "SW_7") (pintype "passive"))
    )
    (net (code "54") (name "Net-(U8-EN)") (class "Default")
      (node (ref "R51") (pin "2") (pinfunction "2_2") (pintype "passive"))
      (node (ref "U8") (pin "3") (pinfunction "EN_3") (pintype "passive"))
    )
    (net (code "55") (name "Net-(U8-NR)") (class "Default")
      (node (ref "C102") (pin "1") (pinfunction "1_1") (pintype "passive"))
      (node (ref "U8") (pin "4") (pinfunction "NR_4") (pintype "passive"))
    )
    (net (code "56") (name "Net-(U9-EN)") (class "Default")
      (node (ref "C107") (pin "1") (pinfunction "1_1") (pintype "passive"))
      (node (ref "R52") (pin "2") (pinfunction "2_2") (pintype "passive"))
      (node (ref "U9") (pin "3") (pinfunction "EN_3") (pintype "passive"))
    )
    (net (code "57") (name "VCC1V0") (class "Default")
      (node (ref "C103") (pin "1") (pinfunction "1_1") (pintype "passive"))
      (node (ref "C105") (pin "1") (pinfunction "1_1") (pintype "passive"))
      (node (ref "L5") (pin "2") (pinfunction "2_2") (pintype "passive"))
      (node (ref "R54") (pin "2") (pinfunction "2_2") (pintype "passive"))
      (node (ref "T14") (pin "1") (pinfunction "TP_1") (pintype "passive"))
    )
    (net (code "58") (name "VCC2V5") (class "Default")
      (node (ref "C106") (pin "1") (pinfunction "1_1") (pintype "passive"))
      (node (ref "T15") (pin "1") (pinfunction "TP_1") (pintype "passive"))
      (node (ref "U8") (pin "5") (pinfunction "OUT_5") (pintype "passive"))
    )
    (net (code "59") (name "VCC5V") (class "Default")
      (node (ref "C104") (pin "1") (pinfunction "1_1") (pintype "passive"))
      (node (ref "C29") (pin "1") (pinfunction "1_1") (pintype "passive"))
      (node (ref "C32") (pin "1") (pinfunction "1_1") (pintype "passive"))
      (node (ref "C68") (pin "2") (pinfunction "2_2") (pintype "passive"))
      (node (ref "C69") (pin "2") (pinfunction "2_2") (pintype "passive"))
      (node (ref "C70") (pin "2") (pinfunction "2_2") (pintype "passive"))
      (node (ref "C73") (pin "2") (pinfunction "2_2") (pintype "passive"))
      (node (ref "R52") (pin "1") (pinfunction "1_1") (pintype "passive"))
      (node (ref "T1") (pin "1") (pinfunction "TP_1") (pintype "passive"))
      (node (ref "U6") (pin "22") (pinfunction "VIN_22") (pintype "passive"))
      (node (ref "U6") (pin "30") (pinfunction "PVIN3_30") (pintype "power_in"))
      (node (ref "U6") (pin "31") (pinfunction "PVIN4_31") (pintype "power_in"))
      (node (ref "U6") (pin "5") (pinfunction "PVIN1_5") (pintype "power_in"))
      (node (ref "U6") (pin "6") (pinfunction "PVIN2_6") (pintype "power_in"))
      (node (ref "U7") (pin "1") (pinfunction "VIN_1") (pintype "passive"))
      (node (ref "U8") (pin "1") (pinfunction "IN_1") (pintype "passive"))
      (node (ref "U9") (pin "1") (pinfunction "VCC_1") (pintype "passive"))
    )
    (net (code "60") (name "VDDD") (class "Default")
      (node (ref "C67") (pin "1") (pinfunction "1_1") (pintype "passive"))
      (node (ref "R25") (pin "1") (pinfunction "1_1") (pintype "passive"))
      (node (ref "R31") (pin "2") (pinfunction "2_2") (pintype "passive"))
      (node (ref "R43") (pin "1") (pinfunction "1_1") (pintype "passive"))
      (node (ref "R47") (pin "2") (pinfunction "2_2") (pintype "passive"))
      (node (ref "R48") (pin "2") (pinfunction "2_2") (pintype "passive"))
      (node (ref "R49") (pin "2") (pinfunction "2_2") (pintype "passive"))
      (node (ref "R53") (pin "2") (pinfunction "2_2") (pintype "passive"))
      (node (ref "U6") (pin "20") (pinfunction "VDDD_20") (pintype "power_in"))
    )
    (net (code "61") (name "unconnected-(U7-PG-Pad6)") (class "Default")
      (node (ref "U7") (pin "6") (pinfunction "PG_6") (pintype "passive+no_connect"))
    )
  )
)
